# icewerks.net
KiCad netlist of a schematic drawn in Altium Designer
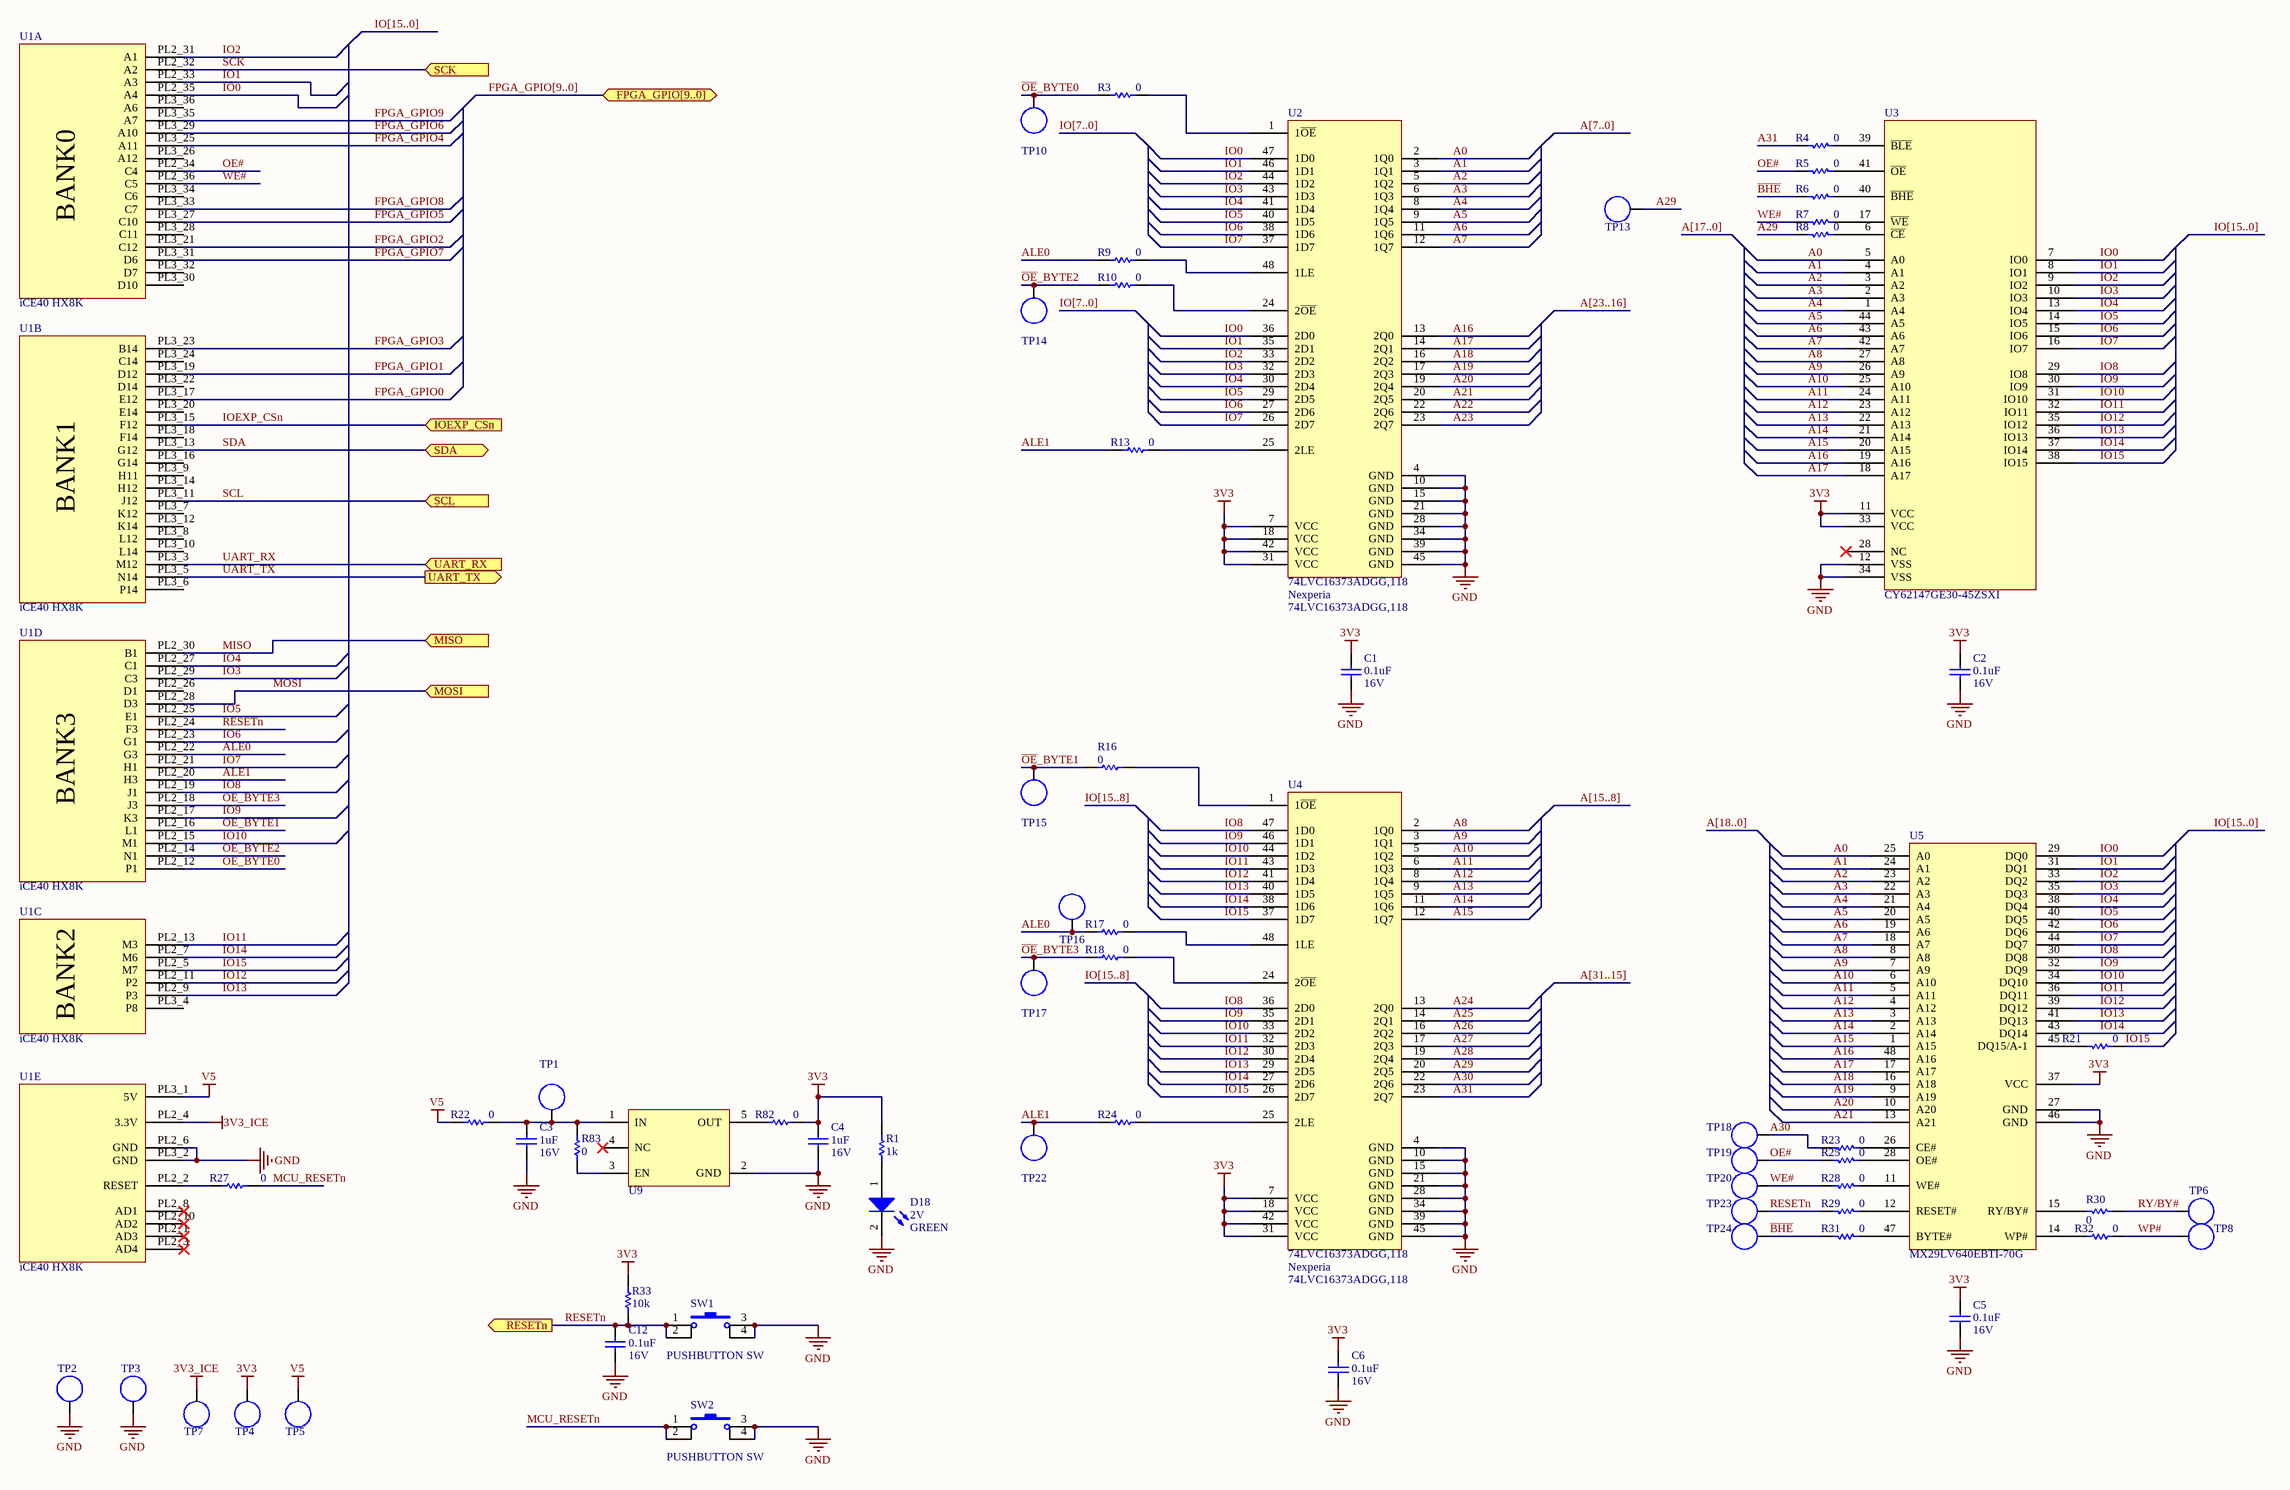
[diagram p0: icewerks.SchDoc]

(export (version "E")
  (design (tool "Eeschema 10.0.6"))
  (components
    (comp (ref "C1")
      (value "Cap_NP")
      (footprint "0805")
      (description "Capacitor")
      (fields
        (field (name "MANUFACTURER") "KEMET")
        (field (name "VOLTAGE") "16V")
        (field (name "CAPACITANCE") "0.1uF")
      )
      (libsource (lib "symbols") (part "Cap_NP"))
    )
    (comp (ref "C2")
      (value "Cap_NP")
      (footprint "0805")
      (description "Capacitor")
      (fields
        (field (name "MANUFACTURER") "KEMET")
        (field (name "VOLTAGE") "16V")
        (field (name "CAPACITANCE") "0.1uF")
      )
      (libsource (lib "symbols") (part "Cap_NP"))
    )
    (comp (ref "C3")
      (value "Cap_NP")
      (footprint "0805")
      (description "Capacitor")
      (fields
        (field (name "MANUFACTURER") "Taiyo Yuden")
        (field (name "VOLTAGE") "16V")
        (field (name "CAPACITANCE") "1uF")
      )
      (libsource (lib "symbols") (part "Cap_NP"))
    )
    (comp (ref "C4")
      (value "Cap_NP")
      (footprint "0805")
      (description "Capacitor")
      (fields
        (field (name "MANUFACTURER") "Taiyo Yuden")
        (field (name "VOLTAGE") "16V")
        (field (name "CAPACITANCE") "1uF")
      )
      (libsource (lib "symbols") (part "Cap_NP"))
    )
    (comp (ref "C5")
      (value "Cap_NP")
      (footprint "0805")
      (description "Capacitor")
      (fields
        (field (name "MANUFACTURER") "KEMET")
        (field (name "VOLTAGE") "16V")
        (field (name "CAPACITANCE") "0.1uF")
      )
      (libsource (lib "symbols") (part "Cap_NP"))
    )
    (comp (ref "C6")
      (value "Cap_NP")
      (footprint "0805")
      (description "Capacitor")
      (fields
        (field (name "MANUFACTURER") "KEMET")
        (field (name "VOLTAGE") "16V")
        (field (name "CAPACITANCE") "0.1uF")
      )
      (libsource (lib "symbols") (part "Cap_NP"))
    )
    (comp (ref "C12")
      (value "Cap_NP")
      (footprint "0805")
      (description "Capacitor")
      (fields
        (field (name "MANUFACTURER") "KEMET")
        (field (name "VOLTAGE") "16V")
        (field (name "CAPACITANCE") "0.1uF")
      )
      (libsource (lib "symbols") (part "Cap_NP"))
    )
    (comp (ref "D18")
      (value "LED")
      (footprint "HSMG-C170")
      (fields
        (field (name "MANUFACTURER") "Broadcom")
        (field (name "VF") "2V")
        (field (name "COLOR") "GREEN")
      )
      (libsource (lib "symbols") (part "LED"))
    )
    (comp (ref "R1")
      (value "Res")
      (footprint "0805")
      (description "Resistor")
      (fields
        (field (name "MANUFACTURER") "Stackpole Electronics Inc")
        (field (name "TOLERANCE") "5%")
        (field (name "RESISTANCE") "1k")
      )
      (libsource (lib "symbols") (part "Res"))
    )
    (comp (ref "R3")
      (value "Res")
      (footprint "0805")
      (description "Resistor")
      (fields
        (field (name "MANUFACTURER") "Stackpole Electronics Inc")
        (field (name "TOLERANCE") "Jumper")
        (field (name "RESISTANCE") "0")
      )
      (libsource (lib "symbols") (part "Res"))
    )
    (comp (ref "R4")
      (value "Res")
      (footprint "0805")
      (description "Resistor")
      (fields
        (field (name "MANUFACTURER") "Stackpole Electronics Inc")
        (field (name "TOLERANCE") "Jumper")
        (field (name "RESISTANCE") "0")
      )
      (libsource (lib "symbols") (part "Res"))
    )
    (comp (ref "R5")
      (value "Res")
      (footprint "0805")
      (description "Resistor")
      (fields
        (field (name "MANUFACTURER") "Stackpole Electronics Inc")
        (field (name "TOLERANCE") "Jumper")
        (field (name "RESISTANCE") "0")
      )
      (libsource (lib "symbols") (part "Res"))
    )
    (comp (ref "R6")
      (value "Res")
      (footprint "0805")
      (description "Resistor")
      (fields
        (field (name "MANUFACTURER") "Stackpole Electronics Inc")
        (field (name "TOLERANCE") "Jumper")
        (field (name "RESISTANCE") "0")
      )
      (libsource (lib "symbols") (part "Res"))
    )
    (comp (ref "R7")
      (value "Res")
      (footprint "0805")
      (description "Resistor")
      (fields
        (field (name "MANUFACTURER") "Stackpole Electronics Inc")
        (field (name "TOLERANCE") "Jumper")
        (field (name "RESISTANCE") "0")
      )
      (libsource (lib "symbols") (part "Res"))
    )
    (comp (ref "R8")
      (value "Res")
      (footprint "0805")
      (description "Resistor")
      (fields
        (field (name "MANUFACTURER") "Stackpole Electronics Inc")
        (field (name "TOLERANCE") "Jumper")
        (field (name "RESISTANCE") "0")
      )
      (libsource (lib "symbols") (part "Res"))
    )
    (comp (ref "R9")
      (value "Res")
      (footprint "0805")
      (description "Resistor")
      (fields
        (field (name "MANUFACTURER") "Stackpole Electronics Inc")
        (field (name "TOLERANCE") "Jumper")
        (field (name "RESISTANCE") "0")
      )
      (libsource (lib "symbols") (part "Res"))
    )
    (comp (ref "R10")
      (value "Res")
      (footprint "0805")
      (description "Resistor")
      (fields
        (field (name "MANUFACTURER") "Stackpole Electronics Inc")
        (field (name "TOLERANCE") "Jumper")
        (field (name "RESISTANCE") "0")
      )
      (libsource (lib "symbols") (part "Res"))
    )
    (comp (ref "R13")
      (value "Res")
      (footprint "0805")
      (description "Resistor")
      (fields
        (field (name "MANUFACTURER") "Stackpole Electronics Inc")
        (field (name "TOLERANCE") "Jumper")
        (field (name "RESISTANCE") "0")
      )
      (libsource (lib "symbols") (part "Res"))
    )
    (comp (ref "R16")
      (value "Res")
      (footprint "0805")
      (description "Resistor")
      (fields
        (field (name "MANUFACTURER") "Stackpole Electronics Inc")
        (field (name "TOLERANCE") "Jumper")
        (field (name "RESISTANCE") "0")
      )
      (libsource (lib "symbols") (part "Res"))
    )
    (comp (ref "R17")
      (value "Res")
      (footprint "0805")
      (description "Resistor")
      (fields
        (field (name "MANUFACTURER") "Stackpole Electronics Inc")
        (field (name "TOLERANCE") "Jumper")
        (field (name "RESISTANCE") "0")
      )
      (libsource (lib "symbols") (part "Res"))
    )
    (comp (ref "R18")
      (value "Res")
      (footprint "0805")
      (description "Resistor")
      (fields
        (field (name "MANUFACTURER") "Stackpole Electronics Inc")
        (field (name "TOLERANCE") "Jumper")
        (field (name "RESISTANCE") "0")
      )
      (libsource (lib "symbols") (part "Res"))
    )
    (comp (ref "R21")
      (value "Res")
      (footprint "0805")
      (description "Resistor")
      (fields
        (field (name "MANUFACTURER") "Stackpole Electronics Inc")
        (field (name "TOLERANCE") "Jumper")
        (field (name "RESISTANCE") "0")
      )
      (libsource (lib "symbols") (part "Res"))
    )
    (comp (ref "R22")
      (value "Res")
      (footprint "0805")
      (description "Resistor")
      (fields
        (field (name "MANUFACTURER") "Stackpole Electronics Inc")
        (field (name "TOLERANCE") "Jumper")
        (field (name "RESISTANCE") "0")
      )
      (libsource (lib "symbols") (part "Res"))
    )
    (comp (ref "R23")
      (value "Res")
      (footprint "0805")
      (description "Resistor")
      (fields
        (field (name "MANUFACTURER") "Stackpole Electronics Inc")
        (field (name "TOLERANCE") "Jumper")
        (field (name "RESISTANCE") "0")
      )
      (libsource (lib "symbols") (part "Res"))
    )
    (comp (ref "R24")
      (value "Res")
      (footprint "0805")
      (description "Resistor")
      (fields
        (field (name "MANUFACTURER") "Stackpole Electronics Inc")
        (field (name "TOLERANCE") "Jumper")
        (field (name "RESISTANCE") "0")
      )
      (libsource (lib "symbols") (part "Res"))
    )
    (comp (ref "R25")
      (value "Res")
      (footprint "0805")
      (description "Resistor")
      (fields
        (field (name "MANUFACTURER") "Stackpole Electronics Inc")
        (field (name "TOLERANCE") "Jumper")
        (field (name "RESISTANCE") "0")
      )
      (libsource (lib "symbols") (part "Res"))
    )
    (comp (ref "R27")
      (value "Res")
      (footprint "0805")
      (description "Resistor")
      (fields
        (field (name "MANUFACTURER") "Stackpole Electronics Inc")
        (field (name "TOLERANCE") "Jumper")
        (field (name "RESISTANCE") "0")
      )
      (libsource (lib "symbols") (part "Res"))
    )
    (comp (ref "R28")
      (value "Res")
      (footprint "0805")
      (description "Resistor")
      (fields
        (field (name "MANUFACTURER") "Stackpole Electronics Inc")
        (field (name "TOLERANCE") "Jumper")
        (field (name "RESISTANCE") "0")
      )
      (libsource (lib "symbols") (part "Res"))
    )
    (comp (ref "R29")
      (value "Res")
      (footprint "0805")
      (description "Resistor")
      (fields
        (field (name "MANUFACTURER") "Stackpole Electronics Inc")
        (field (name "TOLERANCE") "Jumper")
        (field (name "RESISTANCE") "0")
      )
      (libsource (lib "symbols") (part "Res"))
    )
    (comp (ref "R30")
      (value "Res")
      (footprint "0805")
      (description "Resistor")
      (fields
        (field (name "MANUFACTURER") "Stackpole Electronics Inc")
        (field (name "TOLERANCE") "Jumper")
        (field (name "RESISTANCE") "0")
      )
      (libsource (lib "symbols") (part "Res"))
    )
    (comp (ref "R31")
      (value "Res")
      (footprint "0805")
      (description "Resistor")
      (fields
        (field (name "MANUFACTURER") "Stackpole Electronics Inc")
        (field (name "TOLERANCE") "Jumper")
        (field (name "RESISTANCE") "0")
      )
      (libsource (lib "symbols") (part "Res"))
    )
    (comp (ref "R32")
      (value "Res")
      (footprint "0805")
      (description "Resistor")
      (fields
        (field (name "MANUFACTURER") "Stackpole Electronics Inc")
        (field (name "TOLERANCE") "Jumper")
        (field (name "RESISTANCE") "0")
      )
      (libsource (lib "symbols") (part "Res"))
    )
    (comp (ref "R33")
      (value "Res")
      (footprint "0805")
      (description "Resistor")
      (fields
        (field (name "MANUFACTURER") "Stackpole Electronics Inc")
        (field (name "TOLERANCE") "5%")
        (field (name "RESISTANCE") "10k")
      )
      (libsource (lib "symbols") (part "Res"))
    )
    (comp (ref "R82")
      (value "Res")
      (footprint "0805")
      (description "Resistor")
      (fields
        (field (name "MANUFACTURER") "Stackpole Electronics Inc")
        (field (name "TOLERANCE") "Jumper")
        (field (name "RESISTANCE") "0")
      )
      (libsource (lib "symbols") (part "Res"))
    )
    (comp (ref "R83")
      (value "Res")
      (footprint "0805")
      (description "Resistor")
      (fields
        (field (name "MANUFACTURER") "Stackpole Electronics Inc")
        (field (name "TOLERANCE") "Jumper")
        (field (name "RESISTANCE") "0")
      )
      (libsource (lib "symbols") (part "Res"))
    )
    (comp (ref "SW1")
      (value "PUSHBUTTON SW")
      (footprint "XKB TS-1187A")
      (fields (field (name "MANUFACTURER") "XKB"))
      (libsource (lib "symbols") (part "SWITCH_PB"))
    )
    (comp (ref "SW2")
      (value "PUSHBUTTON SW")
      (footprint "XKB TS-1187A")
      (fields (field (name "MANUFACTURER") "XKB"))
      (libsource (lib "symbols") (part "SWITCH_PB"))
    )
    (comp (ref "TP1")
      (value "TP")
      (footprint "KEYSTONE_5012")
      (fields (field (name "MANUFACTURER") "Keystone"))
      (libsource (lib "symbols") (part "TP"))
    )
    (comp (ref "TP2")
      (value "TP")
      (footprint "KEYSTONE_5012")
      (fields (field (name "MANUFACTURER") "Keystone"))
      (libsource (lib "symbols") (part "TP"))
    )
    (comp (ref "TP3")
      (value "TP")
      (footprint "KEYSTONE_5012")
      (fields (field (name "MANUFACTURER") "Keystone"))
      (libsource (lib "symbols") (part "TP"))
    )
    (comp (ref "TP4")
      (value "TP")
      (footprint "KEYSTONE_5012")
      (fields (field (name "MANUFACTURER") "Keystone"))
      (libsource (lib "symbols") (part "TP"))
    )
    (comp (ref "TP5")
      (value "TP")
      (footprint "KEYSTONE_5012")
      (fields (field (name "MANUFACTURER") "Keystone"))
      (libsource (lib "symbols") (part "TP"))
    )
    (comp (ref "TP6")
      (value "TP")
      (footprint "KEYSTONE_5012")
      (fields (field (name "MANUFACTURER") "Keystone"))
      (libsource (lib "symbols") (part "TP"))
    )
    (comp (ref "TP7")
      (value "TP")
      (footprint "KEYSTONE_5012")
      (fields (field (name "MANUFACTURER") "Keystone"))
      (libsource (lib "symbols") (part "TP"))
    )
    (comp (ref "TP8")
      (value "TP")
      (footprint "KEYSTONE_5012")
      (fields (field (name "MANUFACTURER") "Keystone"))
      (libsource (lib "symbols") (part "TP"))
    )
    (comp (ref "TP10")
      (value "TP")
      (footprint "KEYSTONE_5012")
      (fields (field (name "MANUFACTURER") "Keystone"))
      (libsource (lib "symbols") (part "TP"))
    )
    (comp (ref "TP13")
      (value "TP")
      (footprint "KEYSTONE_5012")
      (fields (field (name "MANUFACTURER") "Keystone"))
      (libsource (lib "symbols") (part "TP"))
    )
    (comp (ref "TP14")
      (value "TP")
      (footprint "KEYSTONE_5012")
      (fields (field (name "MANUFACTURER") "Keystone"))
      (libsource (lib "symbols") (part "TP"))
    )
    (comp (ref "TP15")
      (value "TP")
      (footprint "KEYSTONE_5012")
      (fields (field (name "MANUFACTURER") "Keystone"))
      (libsource (lib "symbols") (part "TP"))
    )
    (comp (ref "TP16")
      (value "TP")
      (footprint "KEYSTONE_5012")
      (fields (field (name "MANUFACTURER") "Keystone"))
      (libsource (lib "symbols") (part "TP"))
    )
    (comp (ref "TP17")
      (value "TP")
      (footprint "KEYSTONE_5012")
      (fields (field (name "MANUFACTURER") "Keystone"))
      (libsource (lib "symbols") (part "TP"))
    )
    (comp (ref "TP18")
      (value "TP")
      (footprint "KEYSTONE_5012")
      (fields (field (name "MANUFACTURER") "Keystone"))
      (libsource (lib "symbols") (part "TP"))
    )
    (comp (ref "TP19")
      (value "TP")
      (footprint "KEYSTONE_5012")
      (fields (field (name "MANUFACTURER") "Keystone"))
      (libsource (lib "symbols") (part "TP"))
    )
    (comp (ref "TP20")
      (value "TP")
      (footprint "KEYSTONE_5012")
      (fields (field (name "MANUFACTURER") "Keystone"))
      (libsource (lib "symbols") (part "TP"))
    )
    (comp (ref "TP22")
      (value "TP")
      (footprint "KEYSTONE_5012")
      (fields (field (name "MANUFACTURER") "Keystone"))
      (libsource (lib "symbols") (part "TP"))
    )
    (comp (ref "TP23")
      (value "TP")
      (footprint "KEYSTONE_5012")
      (fields (field (name "MANUFACTURER") "Keystone"))
      (libsource (lib "symbols") (part "TP"))
    )
    (comp (ref "TP24")
      (value "TP")
      (footprint "KEYSTONE_5012")
      (fields (field (name "MANUFACTURER") "Keystone"))
      (libsource (lib "symbols") (part "TP"))
    )
    (comp (ref "U1")
      (value "iCE40 HX8K")
      (footprint "iCE40 HX8K FPGA MODULE")
      (fields (field (name "MANUFACTURER") "Samtec"))
      (libsource (lib "symbols") (part "iCE40 HX8K FPGA MODULE"))
    )
    (comp (ref "U2")
      (value "74LVC16373ADGG,118")
      (footprint "NEXPERIA TSSOP-48 (SOT362-1)")
      (description "D-Type Transparent Latch 2 Channel 8:8 IC Tri-State 48-TSSOP")
      (fields (field (name "MANUFACTURER") "Nexperia") (field (name "MANUFACTURER PN") "74LVC16373ADGG,118"))
      (libsource (lib "symbols") (part "74LVC16373ADGG,118"))
    )
    (comp (ref "U3")
      (value "CY62147GE30-45ZSXI")
      (footprint "CYPRESS Z44 44-TSOP II")
      (description "SRAM - Asynchronous Memory IC 4Mb (256K x 16) Parallel 45ns 44-TSOP II")
      (fields (field (name "MANUFACTURER") "Cypress"))
      (libsource (lib "symbols") (part "CY62147GE30-45ZSXI"))
    )
    (comp (ref "U4")
      (value "74LVC16373ADGG,118")
      (footprint "NEXPERIA TSSOP-48 (SOT362-1)")
      (description "D-Type Transparent Latch 2 Channel 8:8 IC Tri-State 48-TSSOP")
      (fields (field (name "MANUFACTURER") "Nexperia") (field (name "MANUFACTURER PN") "74LVC16373ADGG,118"))
      (libsource (lib "symbols") (part "74LVC16373ADGG,118"))
    )
    (comp (ref "U5")
      (value "MX29LV640EBTI-70G")
      (description "FLASH - NOR Memory IC 8Mb (1M x 8, 512K x 16) Parallel  70ns 48-TSOP")
      (fields (field (name "MANUFACTURER") "Macronix"))
      (libsource (lib "symbols") (part "MX29LV640EBTI-70G"))
    )
    (comp (ref "U9")
      (value "TLV73333PDBVR")
      (footprint "TI DBV0005A (SOT23-5)")
      (fields (field (name "MANUFACTURER") "Texas Instruments"))
      (libsource (lib "symbols") (part "TLV73333PDBVR"))
    )
  )
  (nets
    (net (code "1") (name "/A0") (class "Default")
      (node (ref "U2") (pin "2") (pinfunction "1Q0_2") (pintype "passive"))
      (node (ref "U3") (pin "5") (pinfunction "A0_5") (pintype "passive"))
      (node (ref "U5") (pin "25") (pinfunction "A0_25") (pintype "passive"))
    )
    (net (code "2") (name "/A1") (class "Default")
      (node (ref "U2") (pin "3") (pinfunction "1Q1_3") (pintype "passive"))
      (node (ref "U3") (pin "4") (pinfunction "A1_4") (pintype "passive"))
      (node (ref "U5") (pin "24") (pinfunction "A1_24") (pintype "passive"))
    )
    (net (code "3") (name "/A2") (class "Default")
      (node (ref "U2") (pin "5") (pinfunction "1Q2_5") (pintype "passive"))
      (node (ref "U3") (pin "3") (pinfunction "A2_3") (pintype "passive"))
      (node (ref "U5") (pin "23") (pinfunction "A2_23") (pintype "passive"))
    )
    (net (code "4") (name "/A3") (class "Default")
      (node (ref "U2") (pin "6") (pinfunction "1Q3_6") (pintype "passive"))
      (node (ref "U3") (pin "2") (pinfunction "A3_2") (pintype "passive"))
      (node (ref "U5") (pin "22") (pinfunction "A3_22") (pintype "passive"))
    )
    (net (code "5") (name "/A4") (class "Default")
      (node (ref "U2") (pin "8") (pinfunction "1Q4_8") (pintype "passive"))
      (node (ref "U3") (pin "1") (pinfunction "A4_1") (pintype "passive"))
      (node (ref "U5") (pin "21") (pinfunction "A4_21") (pintype "passive"))
    )
    (net (code "6") (name "/A5") (class "Default")
      (node (ref "U2") (pin "9") (pinfunction "1Q5_9") (pintype "passive"))
      (node (ref "U3") (pin "44") (pinfunction "A5_44") (pintype "passive"))
      (node (ref "U5") (pin "20") (pinfunction "A5_20") (pintype "passive"))
    )
    (net (code "7") (name "/A6") (class "Default")
      (node (ref "U2") (pin "11") (pinfunction "1Q6_11") (pintype "passive"))
      (node (ref "U3") (pin "43") (pinfunction "A6_43") (pintype "passive"))
      (node (ref "U5") (pin "19") (pinfunction "A6_19") (pintype "passive"))
    )
    (net (code "8") (name "/A7") (class "Default")
      (node (ref "U2") (pin "12") (pinfunction "1Q7_12") (pintype "passive"))
      (node (ref "U3") (pin "42") (pinfunction "A7_42") (pintype "passive"))
      (node (ref "U5") (pin "18") (pinfunction "A7_18") (pintype "passive"))
    )
    (net (code "9") (name "/A8") (class "Default")
      (node (ref "U3") (pin "27") (pinfunction "A8_27") (pintype "passive"))
      (node (ref "U4") (pin "2") (pinfunction "1Q0_2") (pintype "passive"))
      (node (ref "U5") (pin "8") (pinfunction "A8_8") (pintype "passive"))
    )
    (net (code "10") (name "/A9") (class "Default")
      (node (ref "U3") (pin "26") (pinfunction "A9_26") (pintype "passive"))
      (node (ref "U4") (pin "3") (pinfunction "1Q1_3") (pintype "passive"))
      (node (ref "U5") (pin "7") (pinfunction "A9_7") (pintype "passive"))
    )
    (net (code "11") (name "/A10") (class "Default")
      (node (ref "U3") (pin "25") (pinfunction "A10_25") (pintype "passive"))
      (node (ref "U4") (pin "5") (pinfunction "1Q2_5") (pintype "passive"))
      (node (ref "U5") (pin "6") (pinfunction "A10_6") (pintype "passive"))
    )
    (net (code "12") (name "/A11") (class "Default")
      (node (ref "U3") (pin "24") (pinfunction "A11_24") (pintype "passive"))
      (node (ref "U4") (pin "6") (pinfunction "1Q3_6") (pintype "passive"))
      (node (ref "U5") (pin "5") (pinfunction "A11_5") (pintype "passive"))
    )
    (net (code "13") (name "/A12") (class "Default")
      (node (ref "U3") (pin "23") (pinfunction "A12_23") (pintype "passive"))
      (node (ref "U4") (pin "8") (pinfunction "1Q4_8") (pintype "passive"))
      (node (ref "U5") (pin "4") (pinfunction "A12_4") (pintype "passive"))
    )
    (net (code "14") (name "/A13") (class "Default")
      (node (ref "U3") (pin "22") (pinfunction "A13_22") (pintype "passive"))
      (node (ref "U4") (pin "9") (pinfunction "1Q5_9") (pintype "passive"))
      (node (ref "U5") (pin "3") (pinfunction "A13_3") (pintype "passive"))
    )
    (net (code "15") (name "/A14") (class "Default")
      (node (ref "U3") (pin "21") (pinfunction "A14_21") (pintype "passive"))
      (node (ref "U4") (pin "11") (pinfunction "1Q6_11") (pintype "passive"))
      (node (ref "U5") (pin "2") (pinfunction "A14_2") (pintype "passive"))
    )
    (net (code "16") (name "/A15") (class "Default")
      (node (ref "U3") (pin "20") (pinfunction "A15_20") (pintype "passive"))
      (node (ref "U4") (pin "12") (pinfunction "1Q7_12") (pintype "passive"))
      (node (ref "U5") (pin "1") (pinfunction "A15_1") (pintype "passive"))
    )
    (net (code "17") (name "/A16") (class "Default")
      (node (ref "U2") (pin "13") (pinfunction "2Q0_13") (pintype "passive"))
      (node (ref "U3") (pin "19") (pinfunction "A16_19") (pintype "passive"))
      (node (ref "U5") (pin "48") (pinfunction "A16_48") (pintype "passive"))
    )
    (net (code "18") (name "/A17") (class "Default")
      (node (ref "U2") (pin "14") (pinfunction "2Q1_14") (pintype "passive"))
      (node (ref "U3") (pin "18") (pinfunction "A17_18") (pintype "passive"))
      (node (ref "U5") (pin "17") (pinfunction "A17_17") (pintype "passive"))
    )
    (net (code "19") (name "/A18") (class "Default")
      (node (ref "U2") (pin "16") (pinfunction "2Q2_16") (pintype "passive"))
      (node (ref "U5") (pin "16") (pinfunction "A18_16") (pintype "passive"))
    )
    (net (code "20") (name "/A19") (class "Default")
      (node (ref "U2") (pin "17") (pinfunction "2Q3_17") (pintype "passive"))
      (node (ref "U5") (pin "9") (pinfunction "A19_9") (pintype "passive"))
    )
    (net (code "21") (name "/A20") (class "Default")
      (node (ref "U2") (pin "19") (pinfunction "2Q4_19") (pintype "passive"))
      (node (ref "U5") (pin "10") (pinfunction "A20_10") (pintype "passive"))
    )
    (net (code "22") (name "/A21") (class "Default")
      (node (ref "U2") (pin "20") (pinfunction "2Q5_20") (pintype "passive"))
      (node (ref "U5") (pin "13") (pinfunction "A21_13") (pintype "passive"))
    )
    (net (code "23") (name "/A22") (class "Default")
      (node (ref "U2") (pin "22") (pinfunction "2Q6_22") (pintype "passive"))
    )
    (net (code "24") (name "/A23") (class "Default")
      (node (ref "U2") (pin "23") (pinfunction "2Q7_23") (pintype "passive"))
    )
    (net (code "25") (name "/A24") (class "Default")
      (node (ref "U4") (pin "13") (pinfunction "2Q0_13") (pintype "passive"))
    )
    (net (code "26") (name "/A25") (class "Default")
      (node (ref "U4") (pin "14") (pinfunction "2Q1_14") (pintype "passive"))
    )
    (net (code "27") (name "/A26") (class "Default")
      (node (ref "U4") (pin "16") (pinfunction "2Q2_16") (pintype "passive"))
    )
    (net (code "28") (name "/A27") (class "Default")
      (node (ref "U4") (pin "17") (pinfunction "2Q3_17") (pintype "passive"))
    )
    (net (code "29") (name "/A28") (class "Default")
      (node (ref "U4") (pin "19") (pinfunction "2Q4_19") (pintype "passive"))
    )
    (net (code "30") (name "/A29") (class "Default")
      (node (ref "R8") (pin "2") (pinfunction "2_2") (pintype "passive"))
      (node (ref "TP13") (pin "1") (pinfunction "1_1") (pintype "passive"))
      (node (ref "U4") (pin "20") (pinfunction "2Q5_20") (pintype "passive"))
    )
    (net (code "31") (name "/A30") (class "Default")
      (node (ref "R23") (pin "2") (pinfunction "2_2") (pintype "passive"))
      (node (ref "TP18") (pin "1") (pinfunction "1_1") (pintype "passive"))
      (node (ref "U4") (pin "22") (pinfunction "2Q6_22") (pintype "passive"))
    )
    (net (code "32") (name "/A31") (class "Default")
      (node (ref "R4") (pin "2") (pinfunction "2_2") (pintype "passive"))
      (node (ref "U4") (pin "23") (pinfunction "2Q7_23") (pintype "passive"))
    )
    (net (code "33") (name "/ALE0") (class "Default")
      (node (ref "R17") (pin "1") (pinfunction "1_1") (pintype "passive"))
      (node (ref "R9") (pin "1") (pinfunction "1_1") (pintype "passive"))
      (node (ref "TP16") (pin "1") (pinfunction "1_1") (pintype "passive"))
      (node (ref "U1") (pin "PL2_22") (pinfunction "G3_PL2_22") (pintype "passive"))
    )
    (net (code "34") (name "/ALE1") (class "Default")
      (node (ref "R13") (pin "1") (pinfunction "1_1") (pintype "passive"))
      (node (ref "R24") (pin "1") (pinfunction "1_1") (pintype "passive"))
      (node (ref "TP22") (pin "1") (pinfunction "1_1") (pintype "passive"))
      (node (ref "U1") (pin "PL2_20") (pinfunction "H3_PL2_20") (pintype "passive"))
    )
    (net (code "41") (name "/FPGA_GPIO0") (class "Default")
      (node (ref "U1") (pin "PL3_17") (pinfunction "E12_PL3_17") (pintype "passive"))
    )
    (net (code "42") (name "/FPGA_GPIO1") (class "Default")
      (node (ref "U1") (pin "PL3_19") (pinfunction "D12_PL3_19") (pintype "passive"))
    )
    (net (code "43") (name "/FPGA_GPIO2") (class "Default")
      (node (ref "U1") (pin "PL3_21") (pinfunction "C12_PL3_21") (pintype "passive"))
    )
    (net (code "44") (name "/FPGA_GPIO3") (class "Default")
      (node (ref "U1") (pin "PL3_23") (pinfunction "B14_PL3_23") (pintype "passive"))
    )
    (net (code "45") (name "/FPGA_GPIO4") (class "Default")
      (node (ref "U1") (pin "PL3_25") (pinfunction "A11_PL3_25") (pintype "passive"))
    )
    (net (code "46") (name "/FPGA_GPIO5") (class "Default")
      (node (ref "U1") (pin "PL3_27") (pinfunction "C10_PL3_27") (pintype "passive"))
    )
    (net (code "47") (name "/FPGA_GPIO6") (class "Default")
      (node (ref "U1") (pin "PL3_29") (pinfunction "A10_PL3_29") (pintype "passive"))
    )
    (net (code "48") (name "/FPGA_GPIO7") (class "Default")
      (node (ref "U1") (pin "PL3_31") (pinfunction "D6_PL3_31") (pintype "passive"))
    )
    (net (code "49") (name "/FPGA_GPIO8") (class "Default")
      (node (ref "U1") (pin "PL3_33") (pinfunction "C7_PL3_33") (pintype "passive"))
    )
    (net (code "50") (name "/FPGA_GPIO9") (class "Default")
      (node (ref "U1") (pin "PL3_35") (pinfunction "A7_PL3_35") (pintype "passive"))
    )
    (net (code "52") (name "/IO0") (class "Default")
      (node (ref "U1") (pin "PL2_35") (pinfunction "A4_PL2_35") (pintype "passive"))
      (node (ref "U2") (pin "36") (pinfunction "2D0_36") (pintype "passive"))
      (node (ref "U2") (pin "47") (pinfunction "1D0_47") (pintype "passive"))
      (node (ref "U3") (pin "7") (pinfunction "IO0_7") (pintype "passive"))
      (node (ref "U5") (pin "29") (pinfunction "DQ0_29") (pintype "passive"))
    )
    (net (code "53") (name "/IO1") (class "Default")
      (node (ref "U1") (pin "PL2_33") (pinfunction "A3_PL2_33") (pintype "passive"))
      (node (ref "U2") (pin "35") (pinfunction "2D1_35") (pintype "passive"))
      (node (ref "U2") (pin "46") (pinfunction "1D1_46") (pintype "passive"))
      (node (ref "U3") (pin "8") (pinfunction "IO1_8") (pintype "passive"))
      (node (ref "U5") (pin "31") (pinfunction "DQ1_31") (pintype "passive"))
    )
    (net (code "54") (name "/IO2") (class "Default")
      (node (ref "U1") (pin "PL2_31") (pinfunction "A1_PL2_31") (pintype "passive"))
      (node (ref "U2") (pin "33") (pinfunction "2D2_33") (pintype "passive"))
      (node (ref "U2") (pin "44") (pinfunction "1D2_44") (pintype "passive"))
      (node (ref "U3") (pin "9") (pinfunction "IO2_9") (pintype "passive"))
      (node (ref "U5") (pin "33") (pinfunction "DQ2_33") (pintype "passive"))
    )
    (net (code "55") (name "/IO3") (class "Default")
      (node (ref "U1") (pin "PL2_29") (pinfunction "C3_PL2_29") (pintype "passive"))
      (node (ref "U2") (pin "32") (pinfunction "2D3_32") (pintype "passive"))
      (node (ref "U2") (pin "43") (pinfunction "1D3_43") (pintype "passive"))
      (node (ref "U3") (pin "10") (pinfunction "IO3_10") (pintype "passive"))
      (node (ref "U5") (pin "35") (pinfunction "DQ3_35") (pintype "passive"))
    )
    (net (code "56") (name "/IO4") (class "Default")
      (node (ref "U1") (pin "PL2_27") (pinfunction "C1_PL2_27") (pintype "passive"))
      (node (ref "U2") (pin "30") (pinfunction "2D4_30") (pintype "passive"))
      (node (ref "U2") (pin "41") (pinfunction "1D4_41") (pintype "passive"))
      (node (ref "U3") (pin "13") (pinfunction "IO4_13") (pintype "passive"))
      (node (ref "U5") (pin "38") (pinfunction "DQ4_38") (pintype "passive"))
    )
    (net (code "57") (name "/IO5") (class "Default")
      (node (ref "U1") (pin "PL2_25") (pinfunction "E1_PL2_25") (pintype "passive"))
      (node (ref "U2") (pin "29") (pinfunction "2D5_29") (pintype "passive"))
      (node (ref "U2") (pin "40") (pinfunction "1D5_40") (pintype "passive"))
      (node (ref "U3") (pin "14") (pinfunction "IO5_14") (pintype "passive"))
      (node (ref "U5") (pin "40") (pinfunction "DQ5_40") (pintype "passive"))
    )
    (net (code "58") (name "/IO6") (class "Default")
      (node (ref "U1") (pin "PL2_23") (pinfunction "G1_PL2_23") (pintype "passive"))
      (node (ref "U2") (pin "27") (pinfunction "2D6_27") (pintype "passive"))
      (node (ref "U2") (pin "38") (pinfunction "1D6_38") (pintype "passive"))
      (node (ref "U3") (pin "15") (pinfunction "IO6_15") (pintype "passive"))
      (node (ref "U5") (pin "42") (pinfunction "DQ6_42") (pintype "passive"))
    )
    (net (code "59") (name "/IO7") (class "Default")
      (node (ref "U1") (pin "PL2_21") (pinfunction "H1_PL2_21") (pintype "passive"))
      (node (ref "U2") (pin "26") (pinfunction "2D7_26") (pintype "passive"))
      (node (ref "U2") (pin "37") (pinfunction "1D7_37") (pintype "passive"))
      (node (ref "U3") (pin "16") (pinfunction "IO7_16") (pintype "passive"))
      (node (ref "U5") (pin "44") (pinfunction "DQ7_44") (pintype "passive"))
    )
    (net (code "60") (name "/IO8") (class "Default")
      (node (ref "U1") (pin "PL2_19") (pinfunction "J1_PL2_19") (pintype "passive"))
      (node (ref "U3") (pin "29") (pinfunction "IO8_29") (pintype "passive"))
      (node (ref "U4") (pin "36") (pinfunction "2D0_36") (pintype "passive"))
      (node (ref "U4") (pin "47") (pinfunction "1D0_47") (pintype "passive"))
      (node (ref "U5") (pin "30") (pinfunction "DQ8_30") (pintype "passive"))
    )
    (net (code "61") (name "/IO9") (class "Default")
      (node (ref "U1") (pin "PL2_17") (pinfunction "K3_PL2_17") (pintype "passive"))
      (node (ref "U3") (pin "30") (pinfunction "IO9_30") (pintype "passive"))
      (node (ref "U4") (pin "35") (pinfunction "2D1_35") (pintype "passive"))
      (node (ref "U4") (pin "46") (pinfunction "1D1_46") (pintype "passive"))
      (node (ref "U5") (pin "32") (pinfunction "DQ9_32") (pintype "passive"))
    )
    (net (code "62") (name "/IO10") (class "Default")
      (node (ref "U1") (pin "PL2_15") (pinfunction "M1_PL2_15") (pintype "passive"))
      (node (ref "U3") (pin "31") (pinfunction "IO10_31") (pintype "passive"))
      (node (ref "U4") (pin "33") (pinfunction "2D2_33") (pintype "passive"))
      (node (ref "U4") (pin "44") (pinfunction "1D2_44") (pintype "passive"))
      (node (ref "U5") (pin "34") (pinfunction "DQ10_34") (pintype "passive"))
    )
    (net (code "63") (name "/IO11") (class "Default")
      (node (ref "U1") (pin "PL2_13") (pinfunction "M3_PL2_13") (pintype "passive"))
      (node (ref "U3") (pin "32") (pinfunction "IO11_32") (pintype "passive"))
      (node (ref "U4") (pin "32") (pinfunction "2D3_32") (pintype "passive"))
      (node (ref "U4") (pin "43") (pinfunction "1D3_43") (pintype "passive"))
      (node (ref "U5") (pin "36") (pinfunction "DQ11_36") (pintype "passive"))
    )
    (net (code "64") (name "/IO12") (class "Default")
      (node (ref "U1") (pin "PL2_11") (pinfunction "P2_PL2_11") (pintype "passive"))
      (node (ref "U3") (pin "35") (pinfunction "IO12_35") (pintype "passive"))
      (node (ref "U4") (pin "30") (pinfunction "2D4_30") (pintype "passive"))
      (node (ref "U4") (pin "41") (pinfunction "1D4_41") (pintype "passive"))
      (node (ref "U5") (pin "39") (pinfunction "DQ12_39") (pintype "passive"))
    )
    (net (code "65") (name "/IO13") (class "Default")
      (node (ref "U1") (pin "PL2_9") (pinfunction "P3_PL2_9") (pintype "passive"))
      (node (ref "U3") (pin "36") (pinfunction "IO13_36") (pintype "passive"))
      (node (ref "U4") (pin "29") (pinfunction "2D5_29") (pintype "passive"))
      (node (ref "U4") (pin "40") (pinfunction "1D5_40") (pintype "passive"))
      (node (ref "U5") (pin "41") (pinfunction "DQ13_41") (pintype "passive"))
    )
    (net (code "66") (name "/IO14") (class "Default")
      (node (ref "U1") (pin "PL2_7") (pinfunction "M6_PL2_7") (pintype "passive"))
      (node (ref "U3") (pin "37") (pinfunction "IO14_37") (pintype "passive"))
      (node (ref "U4") (pin "27") (pinfunction "2D6_27") (pintype "passive"))
      (node (ref "U4") (pin "38") (pinfunction "1D6_38") (pintype "passive"))
      (node (ref "U5") (pin "43") (pinfunction "DQ14_43") (pintype "passive"))
    )
    (net (code "67") (name "/IO15") (class "Default")
      (node (ref "R21") (pin "1") (pinfunction "1_1") (pintype "passive"))
      (node (ref "U1") (pin "PL2_5") (pinfunction "M7_PL2_5") (pintype "passive"))
      (node (ref "U3") (pin "38") (pinfunction "IO15_38") (pintype "passive"))
      (node (ref "U4") (pin "26") (pinfunction "2D7_26") (pintype "passive"))
      (node (ref "U4") (pin "37") (pinfunction "1D7_37") (pintype "passive"))
    )
    (net (code "68") (name "/IOEXP_CSn") (class "Default")
      (node (ref "U1") (pin "PL3_15") (pinfunction "F12_PL3_15") (pintype "passive"))
    )
    (net (code "72") (name "/MCU_RESETn") (class "Default")
      (node (ref "R27") (pin "2") (pinfunction "2_2") (pintype "passive"))
      (node (ref "SW2") (pin "1") (pinfunction "1_1") (pintype "passive"))
      (node (ref "SW2") (pin "2") (pinfunction "2_2") (pintype "passive"))
    )
    (net (code "73") (name "/MISO") (class "Default")
      (node (ref "U1") (pin "PL2_30") (pinfunction "B1_PL2_30") (pintype "passive"))
    )
    (net (code "74") (name "/MOSI") (class "Default")
      (node (ref "U1") (pin "PL2_28") (pinfunction "D3_PL2_28") (pintype "passive"))
    )
    (net (code "75") (name "/OE#") (class "Default")
      (node (ref "R25") (pin "2") (pinfunction "2_2") (pintype "passive"))
      (node (ref "R5") (pin "2") (pinfunction "2_2") (pintype "passive"))
      (node (ref "TP19") (pin "1") (pinfunction "1_1") (pintype "passive"))
      (node (ref "U1") (pin "PL2_34") (pinfunction "C4_PL2_34") (pintype "passive"))
    )
    (net (code "76") (name "/RESETn") (class "Default")
      (node (ref "C12") (pin "2") (pinfunction "2_2") (pintype "passive"))
      (node (ref "R29") (pin "2") (pinfunction "2_2") (pintype "passive"))
      (node (ref "R33") (pin "1") (pinfunction "1_1") (pintype "passive"))
      (node (ref "SW1") (pin "1") (pinfunction "1_1") (pintype "passive"))
      (node (ref "SW1") (pin "2") (pinfunction "2_2") (pintype "passive"))
      (node (ref "TP23") (pin "1") (pinfunction "1_1") (pintype "passive"))
      (node (ref "U1") (pin "PL2_24") (pinfunction "F3_PL2_24") (pintype "passive"))
    )
    (net (code "77") (name "/RY{slash}BY#") (class "Default")
      (node (ref "R30") (pin "1") (pinfunction "1_1") (pintype "passive"))
      (node (ref "TP6") (pin "1") (pinfunction "1_1") (pintype "passive"))
    )
    (net (code "78") (name "/SCK") (class "Default")
      (node (ref "U1") (pin "PL2_32") (pinfunction "A2_PL2_32") (pintype "passive"))
    )
    (net (code "79") (name "/SCL") (class "Default")
      (node (ref "U1") (pin "PL3_11") (pinfunction "J12_PL3_11") (pintype "passive"))
    )
    (net (code "80") (name "/SDA") (class "Default")
      (node (ref "U1") (pin "PL3_13") (pinfunction "G12_PL3_13") (pintype "passive"))
    )
    (net (code "81") (name "/UART_RX") (class "Default")
      (node (ref "U1") (pin "PL3_3") (pinfunction "M12_PL3_3") (pintype "passive"))
    )
    (net (code "82") (name "/UART_TX") (class "Default")
      (node (ref "U1") (pin "PL3_5") (pinfunction "N14_PL3_5") (pintype "passive"))
    )
    (net (code "83") (name "/WE#") (class "Default")
      (node (ref "R28") (pin "2") (pinfunction "2_2") (pintype "passive"))
      (node (ref "R7") (pin "2") (pinfunction "2_2") (pintype "passive"))
      (node (ref "TP20") (pin "1") (pinfunction "1_1") (pintype "passive"))
      (node (ref "U1") (pin "PL2_36") (pinfunction "C5_PL2_36") (pintype "passive"))
    )
    (net (code "84") (name "/WP#") (class "Default")
      (node (ref "R32") (pin "2") (pinfunction "2_2") (pintype "passive"))
      (node (ref "TP8") (pin "1") (pinfunction "1_1") (pintype "passive"))
    )
    (net (code "85") (name "/~{BHE}") (class "Default")
      (node (ref "R31") (pin "2") (pinfunction "2_2") (pintype "passive"))
      (node (ref "R6") (pin "2") (pinfunction "2_2") (pintype "passive"))
      (node (ref "TP24") (pin "1") (pinfunction "1_1") (pintype "passive"))
    )
    (net (code "86") (name "/~{OE}_BYTE0") (class "Default")
      (node (ref "R3") (pin "1") (pinfunction "1_1") (pintype "passive"))
      (node (ref "TP10") (pin "1") (pinfunction "1_1") (pintype "passive"))
      (node (ref "U1") (pin "PL2_12") (pinfunction "P1_PL2_12") (pintype "passive"))
    )
    (net (code "87") (name "/~{OE}_BYTE1") (class "Default")
      (node (ref "R16") (pin "1") (pinfunction "1_1") (pintype "passive"))
      (node (ref "TP15") (pin "1") (pinfunction "1_1") (pintype "passive"))
      (node (ref "U1") (pin "PL2_16") (pinfunction "L1_PL2_16") (pintype "passive"))
    )
    (net (code "88") (name "/~{OE}_BYTE2") (class "Default")
      (node (ref "R10") (pin "1") (pinfunction "1_1") (pintype "passive"))
      (node (ref "TP14") (pin "1") (pinfunction "1_1") (pintype "passive"))
      (node (ref "U1") (pin "PL2_14") (pinfunction "N1_PL2_14") (pintype "passive"))
    )
    (net (code "89") (name "/~{OE}_BYTE3") (class "Default")
      (node (ref "R18") (pin "1") (pinfunction "1_1") (pintype "passive"))
      (node (ref "TP17") (pin "1") (pinfunction "1_1") (pintype "passive"))
      (node (ref "U1") (pin "PL2_18") (pinfunction "J3_PL2_18") (pintype "passive"))
    )
    (net (code "90") (name "3V3") (class "Default")
      (node (ref "C1") (pin "2") (pinfunction "2_2") (pintype "passive"))
      (node (ref "C2") (pin "2") (pinfunction "2_2") (pintype "passive"))
      (node (ref "C4") (pin "2") (pinfunction "2_2") (pintype "passive"))
      (node (ref "C5") (pin "2") (pinfunction "2_2") (pintype "passive"))
      (node (ref "C6") (pin "2") (pinfunction "2_2") (pintype "passive"))
      (node (ref "R1") (pin "2") (pinfunction "2_2") (pintype "passive"))
      (node (ref "R33") (pin "2") (pinfunction "2_2") (pintype "passive"))
      (node (ref "R82") (pin "2") (pinfunction "2_2") (pintype "passive"))
      (node (ref "TP4") (pin "1") (pinfunction "1_1") (pintype "passive"))
      (node (ref "U2") (pin "18") (pinfunction "VCC_18") (pintype "passive"))
      (node (ref "U2") (pin "31") (pinfunction "VCC_31") (pintype "passive"))
      (node (ref "U2") (pin "42") (pinfunction "VCC_42") (pintype "passive"))
      (node (ref "U2") (pin "7") (pinfunction "VCC_7") (pintype "passive"))
      (node (ref "U3") (pin "11") (pinfunction "VCC_11") (pintype "passive"))
      (node (ref "U3") (pin "33") (pinfunction "VCC_33") (pintype "passive"))
      (node (ref "U4") (pin "18") (pinfunction "VCC_18") (pintype "passive"))
      (node (ref "U4") (pin "31") (pinfunction "VCC_31") (pintype "passive"))
      (node (ref "U4") (pin "42") (pinfunction "VCC_42") (pintype "passive"))
      (node (ref "U4") (pin "7") (pinfunction "VCC_7") (pintype "passive"))
      (node (ref "U5") (pin "37") (pinfunction "VCC_37") (pintype "passive"))
    )
    (net (code "91") (name "3V3_ICE") (class "Default")
      (node (ref "TP7") (pin "1") (pinfunction "1_1") (pintype "passive"))
      (node (ref "U1") (pin "PL2_4") (pinfunction "3.3V_PL2_4") (pintype "passive"))
    )
    (net (code "92") (name "GND") (class "Default")
      (node (ref "C1") (pin "1") (pinfunction "1_1") (pintype "passive"))
      (node (ref "C12") (pin "1") (pinfunction "1_1") (pintype "passive"))
      (node (ref "C2") (pin "1") (pinfunction "1_1") (pintype "passive"))
      (node (ref "C3") (pin "1") (pinfunction "1_1") (pintype "passive"))
      (node (ref "C4") (pin "1") (pinfunction "1_1") (pintype "passive"))
      (node (ref "C5") (pin "1") (pinfunction "1_1") (pintype "passive"))
      (node (ref "C6") (pin "1") (pinfunction "1_1") (pintype "passive"))
      (node (ref "D18") (pin "2") (pinfunction "K_2") (pintype "passive"))
      (node (ref "SW1") (pin "3") (pinfunction "3_3") (pintype "passive"))
      (node (ref "SW1") (pin "4") (pinfunction "4_4") (pintype "passive"))
      (node (ref "SW2") (pin "3") (pinfunction "3_3") (pintype "passive"))
      (node (ref "SW2") (pin "4") (pinfunction "4_4") (pintype "passive"))
      (node (ref "TP2") (pin "1") (pinfunction "1_1") (pintype "passive"))
      (node (ref "TP3") (pin "1") (pinfunction "1_1") (pintype "passive"))
      (node (ref "U1") (pin "PL2_6") (pinfunction "GND_PL2_6") (pintype "passive"))
      (node (ref "U1") (pin "PL3_2") (pinfunction "GND_PL3_2") (pintype "passive"))
      (node (ref "U2") (pin "10") (pinfunction "GND_10") (pintype "passive"))
      (node (ref "U2") (pin "15") (pinfunction "GND_15") (pintype "passive"))
      (node (ref "U2") (pin "21") (pinfunction "GND_21") (pintype "passive"))
      (node (ref "U2") (pin "28") (pinfunction "GND_28") (pintype "passive"))
      (node (ref "U2") (pin "34") (pinfunction "GND_34") (pintype "passive"))
      (node (ref "U2") (pin "39") (pinfunction "GND_39") (pintype "passive"))
      (node (ref "U2") (pin "4") (pinfunction "GND_4") (pintype "passive"))
      (node (ref "U2") (pin "45") (pinfunction "GND_45") (pintype "passive"))
      (node (ref "U3") (pin "12") (pinfunction "VSS_12") (pintype "passive"))
      (node (ref "U3") (pin "34") (pinfunction "VSS_34") (pintype "passive"))
      (node (ref "U4") (pin "10") (pinfunction "GND_10") (pintype "passive"))
      (node (ref "U4") (pin "15") (pinfunction "GND_15") (pintype "passive"))
      (node (ref "U4") (pin "21") (pinfunction "GND_21") (pintype "passive"))
      (node (ref "U4") (pin "28") (pinfunction "GND_28") (pintype "passive"))
      (node (ref "U4") (pin "34") (pinfunction "GND_34") (pintype "passive"))
      (node (ref "U4") (pin "39") (pinfunction "GND_39") (pintype "passive"))
      (node (ref "U4") (pin "4") (pinfunction "GND_4") (pintype "passive"))
      (node (ref "U4") (pin "45") (pinfunction "GND_45") (pintype "passive"))
      (node (ref "U5") (pin "27") (pinfunction "GND_27") (pintype "passive"))
      (node (ref "U5") (pin "46") (pinfunction "GND_46") (pintype "passive"))
      (node (ref "U9") (pin "2") (pinfunction "GND_2") (pintype "passive"))
    )
    (net (code "93") (name "Net-(D18-A)") (class "Default")
      (node (ref "D18") (pin "1") (pinfunction "A_1") (pintype "passive"))
      (node (ref "R1") (pin "1") (pinfunction "1_1") (pintype "passive"))
    )
    (net (code "94") (name "Net-(U1E-RESET)") (class "Default")
      (node (ref "R27") (pin "1") (pinfunction "1_1") (pintype "passive"))
      (node (ref "U1") (pin "PL2_2") (pinfunction "RESET_PL2_2") (pintype "passive"))
    )
    (net (code "95") (name "Net-(U2-1LE)") (class "Default")
      (node (ref "R9") (pin "2") (pinfunction "2_2") (pintype "passive"))
      (node (ref "U2") (pin "48") (pinfunction "1LE_48") (pintype "passive"))
    )
    (net (code "96") (name "Net-(U2-1~{OE})") (class "Default")
      (node (ref "R3") (pin "2") (pinfunction "2_2") (pintype "passive"))
      (node (ref "U2") (pin "1") (pinfunction "1~{OE}_1") (pintype "passive"))
    )
    (net (code "97") (name "Net-(U2-2LE)") (class "Default")
      (node (ref "R13") (pin "2") (pinfunction "2_2") (pintype "passive"))
      (node (ref "U2") (pin "25") (pinfunction "2LE_25") (pintype "passive"))
    )
    (net (code "98") (name "Net-(U2-2~{OE})") (class "Default")
      (node (ref "R10") (pin "2") (pinfunction "2_2") (pintype "passive"))
      (node (ref "U2") (pin "24") (pinfunction "2~{OE}_24") (pintype "passive"))
    )
    (net (code "99") (name "Net-(U3-~{BHE})") (class "Default")
      (node (ref "R6") (pin "1") (pinfunction "1_1") (pintype "passive"))
      (node (ref "U3") (pin "40") (pinfunction "~{BHE}_40") (pintype "passive"))
    )
    (net (code "100") (name "Net-(U3-~{BLE})") (class "Default")
      (node (ref "R4") (pin "1") (pinfunction "1_1") (pintype "passive"))
      (node (ref "U3") (pin "39") (pinfunction "~{BLE}_39") (pintype "passive"))
    )
    (net (code "101") (name "Net-(U3-~{CE})") (class "Default")
      (node (ref "R8") (pin "1") (pinfunction "1_1") (pintype "passive"))
      (node (ref "U3") (pin "6") (pinfunction "~{CE}_6") (pintype "passive"))
    )
    (net (code "102") (name "Net-(U3-~{OE})") (class "Default")
      (node (ref "R5") (pin "1") (pinfunction "1_1") (pintype "passive"))
      (node (ref "U3") (pin "41") (pinfunction "~{OE}_41") (pintype "passive"))
    )
    (net (code "103") (name "Net-(U3-~{WE})") (class "Default")
      (node (ref "R7") (pin "1") (pinfunction "1_1") (pintype "passive"))
      (node (ref "U3") (pin "17") (pinfunction "~{WE}_17") (pintype "passive"))
    )
    (net (code "104") (name "Net-(U4-1LE)") (class "Default")
      (node (ref "R17") (pin "2") (pinfunction "2_2") (pintype "passive"))
      (node (ref "U4") (pin "48") (pinfunction "1LE_48") (pintype "passive"))
    )
    (net (code "105") (name "Net-(U4-1~{OE})") (class "Default")
      (node (ref "R16") (pin "2") (pinfunction "2_2") (pintype "passive"))
      (node (ref "U4") (pin "1") (pinfunction "1~{OE}_1") (pintype "passive"))
    )
    (net (code "106") (name "Net-(U4-2LE)") (class "Default")
      (node (ref "R24") (pin "2") (pinfunction "2_2") (pintype "passive"))
      (node (ref "U4") (pin "25") (pinfunction "2LE_25") (pintype "passive"))
    )
    (net (code "107") (name "Net-(U4-2~{OE})") (class "Default")
      (node (ref "R18") (pin "2") (pinfunction "2_2") (pintype "passive"))
      (node (ref "U4") (pin "24") (pinfunction "2~{OE}_24") (pintype "passive"))
    )
    (net (code "108") (name "Net-(U5-BYTE#)") (class "Default")
      (node (ref "R31") (pin "1") (pinfunction "1_1") (pintype "passive"))
      (node (ref "U5") (pin "47") (pinfunction "BYTE#_47") (pintype "passive"))
    )
    (net (code "109") (name "Net-(U5-CE#)") (class "Default")
      (node (ref "R23") (pin "1") (pinfunction "1_1") (pintype "passive"))
      (node (ref "U5") (pin "26") (pinfunction "CE#_26") (pintype "passive"))
    )
    (net (code "110") (name "Net-(U5-DQ15{slash}A-1)") (class "Default")
      (node (ref "R21") (pin "2") (pinfunction "2_2") (pintype "passive"))
      (node (ref "U5") (pin "45") (pinfunction "DQ15/A-1_45") (pintype "passive"))
    )
    (net (code "111") (name "Net-(U5-OE#)") (class "Default")
      (node (ref "R25") (pin "1") (pinfunction "1_1") (pintype "passive"))
      (node (ref "U5") (pin "28") (pinfunction "OE#_28") (pintype "passive"))
    )
    (net (code "112") (name "Net-(U5-RESET#)") (class "Default")
      (node (ref "R29") (pin "1") (pinfunction "1_1") (pintype "passive"))
      (node (ref "U5") (pin "12") (pinfunction "RESET#_12") (pintype "passive"))
    )
    (net (code "113") (name "Net-(U5-RY{slash}BY#)") (class "Default")
      (node (ref "R30") (pin "2") (pinfunction "2_2") (pintype "passive"))
      (node (ref "U5") (pin "15") (pinfunction "RY/BY#_15") (pintype "passive"))
    )
    (net (code "114") (name "Net-(U5-WE#)") (class "Default")
      (node (ref "R28") (pin "1") (pinfunction "1_1") (pintype "passive"))
      (node (ref "U5") (pin "11") (pinfunction "WE#_11") (pintype "passive"))
    )
    (net (code "115") (name "Net-(U5-WP#)") (class "Default")
      (node (ref "R32") (pin "1") (pinfunction "1_1") (pintype "passive"))
      (node (ref "U5") (pin "14") (pinfunction "WP#_14") (pintype "passive"))
    )
    (net (code "116") (name "Net-(U9-EN)") (class "Default")
      (node (ref "R83") (pin "1") (pinfunction "1_1") (pintype "passive"))
      (node (ref "U9") (pin "3") (pinfunction "EN_3") (pintype "passive"))
    )
    (net (code "117") (name "Net-(U9-IN)") (class "Default")
      (node (ref "C3") (pin "2") (pinfunction "2_2") (pintype "passive"))
      (node (ref "R22") (pin "2") (pinfunction "2_2") (pintype "passive"))
      (node (ref "R83") (pin "2") (pinfunction "2_2") (pintype "passive"))
      (node (ref "TP1") (pin "1") (pinfunction "1_1") (pintype "passive"))
      (node (ref "U9") (pin "1") (pinfunction "IN_1") (pintype "passive"))
    )
    (net (code "118") (name "Net-(U9-OUT)") (class "Default")
      (node (ref "R82") (pin "1") (pinfunction "1_1") (pintype "passive"))
      (node (ref "U9") (pin "5") (pinfunction "OUT_5") (pintype "passive"))
    )
    (net (code "119") (name "V5") (class "Default")
      (node (ref "R22") (pin "1") (pinfunction "1_1") (pintype "passive"))
      (node (ref "TP5") (pin "1") (pinfunction "1_1") (pintype "passive"))
      (node (ref "U1") (pin "PL3_1") (pinfunction "5V_PL3_1") (pintype "passive"))
    )
    (net (code "120") (name "unconnected-(U1A-A6-PadPL3_36)") (class "Default")
      (node (ref "U1") (pin "PL3_36") (pinfunction "A6_PL3_36") (pintype "passive"))
    )
    (net (code "121") (name "unconnected-(U1A-A12-PadPL3_26)") (class "Default")
      (node (ref "U1") (pin "PL3_26") (pinfunction "A12_PL3_26") (pintype "passive"))
    )
    (net (code "122") (name "unconnected-(U1A-C6-PadPL3_34)") (class "Default")
      (node (ref "U1") (pin "PL3_34") (pinfunction "C6_PL3_34") (pintype "passive"))
    )
    (net (code "123") (name "unconnected-(U1A-C11-PadPL3_28)") (class "Default")
      (node (ref "U1") (pin "PL3_28") (pinfunction "C11_PL3_28") (pintype "passive"))
    )
    (net (code "124") (name "unconnected-(U1A-D7-PadPL3_32)") (class "Default")
      (node (ref "U1") (pin "PL3_32") (pinfunction "D7_PL3_32") (pintype "passive"))
    )
    (net (code "125") (name "unconnected-(U1A-D10-PadPL3_30)") (class "Default")
      (node (ref "U1") (pin "PL3_30") (pinfunction "D10_PL3_30") (pintype "passive"))
    )
    (net (code "126") (name "unconnected-(U1B-C14-PadPL3_24)") (class "Default")
      (node (ref "U1") (pin "PL3_24") (pinfunction "C14_PL3_24") (pintype "passive"))
    )
    (net (code "127") (name "unconnected-(U1B-D14-PadPL3_22)") (class "Default")
      (node (ref "U1") (pin "PL3_22") (pinfunction "D14_PL3_22") (pintype "passive"))
    )
    (net (code "128") (name "unconnected-(U1B-E14-PadPL3_20)") (class "Default")
      (node (ref "U1") (pin "PL3_20") (pinfunction "E14_PL3_20") (pintype "passive"))
    )
    (net (code "129") (name "unconnected-(U1B-F14-PadPL3_18)") (class "Default")
      (node (ref "U1") (pin "PL3_18") (pinfunction "F14_PL3_18") (pintype "passive"))
    )
    (net (code "130") (name "unconnected-(U1B-G14-PadPL3_16)") (class "Default")
      (node (ref "U1") (pin "PL3_16") (pinfunction "G14_PL3_16") (pintype "passive"))
    )
    (net (code "131") (name "unconnected-(U1B-H11-PadPL3_9)") (class "Default")
      (node (ref "U1") (pin "PL3_9") (pinfunction "H11_PL3_9") (pintype "passive"))
    )
    (net (code "132") (name "unconnected-(U1B-H12-PadPL3_14)") (class "Default")
      (node (ref "U1") (pin "PL3_14") (pinfunction "H12_PL3_14") (pintype "passive"))
    )
    (net (code "133") (name "unconnected-(U1B-K12-PadPL3_7)") (class "Default")
      (node (ref "U1") (pin "PL3_7") (pinfunction "K12_PL3_7") (pintype "passive"))
    )
    (net (code "134") (name "unconnected-(U1B-K14-PadPL3_12)") (class "Default")
      (node (ref "U1") (pin "PL3_12") (pinfunction "K14_PL3_12") (pintype "passive"))
    )
    (net (code "135") (name "unconnected-(U1B-L12-PadPL3_8)") (class "Default")
      (node (ref "U1") (pin "PL3_8") (pinfunction "L12_PL3_8") (pintype "passive"))
    )
    (net (code "136") (name "unconnected-(U1B-L14-PadPL3_10)") (class "Default")
      (node (ref "U1") (pin "PL3_10") (pinfunction "L14_PL3_10") (pintype "passive"))
    )
    (net (code "137") (name "unconnected-(U1B-P14-PadPL3_6)") (class "Default")
      (node (ref "U1") (pin "PL3_6") (pinfunction "P14_PL3_6") (pintype "passive"))
    )
    (net (code "138") (name "unconnected-(U1C-P8-PadPL3_4)") (class "Default")
      (node (ref "U1") (pin "PL3_4") (pinfunction "P8_PL3_4") (pintype "passive"))
    )
    (net (code "139") (name "unconnected-(U1D-D1-PadPL2_26)") (class "Default")
      (node (ref "U1") (pin "PL2_26") (pinfunction "D1_PL2_26") (pintype "passive"))
    )
    (net (code "140") (name "unconnected-(U1E-AD1-PadPL2_8)") (class "Default")
      (node (ref "U1") (pin "PL2_8") (pinfunction "AD1_PL2_8") (pintype "passive+no_connect"))
    )
    (net (code "141") (name "unconnected-(U1E-AD2-PadPL2_10)") (class "Default")
      (node (ref "U1") (pin "PL2_10") (pinfunction "AD2_PL2_10") (pintype "passive+no_connect"))
    )
    (net (code "142") (name "unconnected-(U1E-AD3-PadPL2_1)") (class "Default")
      (node (ref "U1") (pin "PL2_1") (pinfunction "AD3_PL2_1") (pintype "passive+no_connect"))
    )
    (net (code "143") (name "unconnected-(U1E-AD4-PadPL2_3)") (class "Default")
      (node (ref "U1") (pin "PL2_3") (pinfunction "AD4_PL2_3") (pintype "passive+no_connect"))
    )
    (net (code "144") (name "unconnected-(U3-NC-Pad28)") (class "Default")
      (node (ref "U3") (pin "28") (pinfunction "NC_28") (pintype "passive+no_connect"))
    )
    (net (code "145") (name "unconnected-(U9-NC-Pad4)") (class "Default")
      (node (ref "U9") (pin "4") (pinfunction "NC_4") (pintype "passive+no_connect"))
    )
  )
)
